# DynamixelController.net
KiCad netlist of a schematic drawn in EAGLE
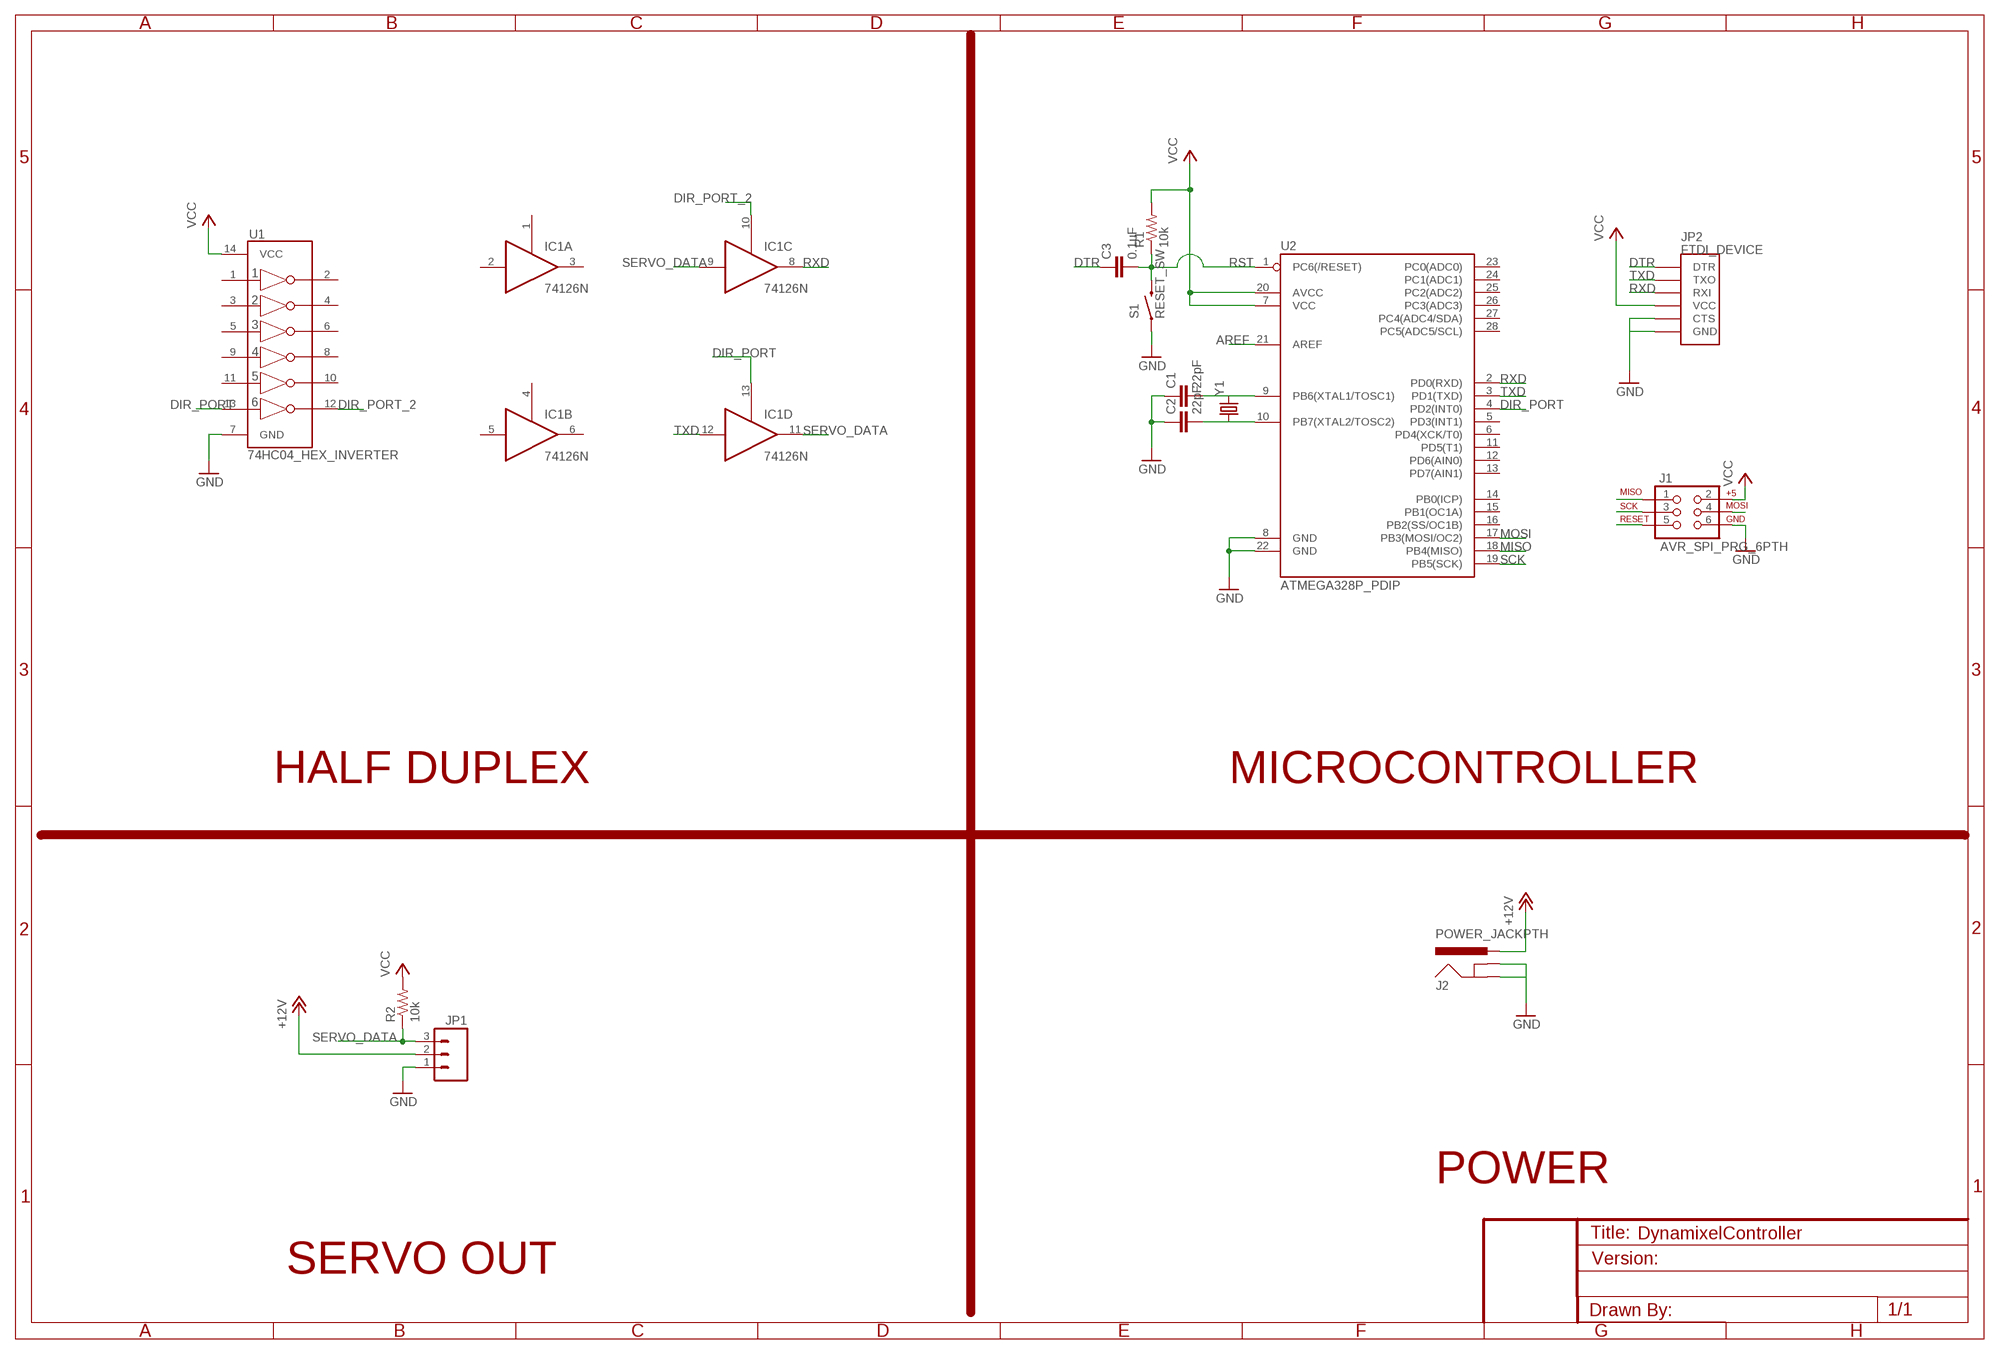
[diagram p0: schematic, sheet 1]

(export (version "E")
  (design (tool "Eeschema 10.0.6"))
  (components
    (comp (ref "C1")
      (value "22pF")
      (footprint "eagle-import:C050-024X044")
      (libsource (lib "eagle-import") (part "C-EU050-024X044"))
    )
    (comp (ref "C2")
      (value "22pF")
      (footprint "eagle-import:C050-024X044")
      (libsource (lib "eagle-import") (part "C-EU050-024X044"))
    )
    (comp (ref "C3")
      (value "0.1uF")
      (footprint "eagle-import:C050-024X044")
      (libsource (lib "eagle-import") (part "C-EU050-024X044"))
    )
    (comp (ref "IC1")
      (value "74126N")
      (footprint "eagle-import:DIL14")
      (libsource (lib "eagle-import") (part "74126N"))
    )
    (comp (ref "J1")
      (value "AVR_SPI_PRG_6PTH")
      (footprint "eagle-import:2X3")
      (libsource (lib "eagle-import") (part "AVR_SPI_PRG_6PTH"))
    )
    (comp (ref "J2")
      (value "POWER_JACKPTH")
      (footprint "eagle-import:POWER_JACK_PTH")
      (libsource (lib "eagle-import") (part "POWER_JACKPTH"))
    )
    (comp (ref "JP1")
      (value "M03POLAR")
      (footprint "eagle-import:MOLEX-1X3")
      (libsource (lib "eagle-import") (part "M03POLAR"))
    )
    (comp (ref "JP2")
      (value "FTDI_DEVICE")
      (footprint "eagle-import:FTDI_DEVICE_SIDE")
      (libsource (lib "eagle-import") (part "FTDI_DEVICE"))
    )
    (comp (ref "R1")
      (value "10k")
      (footprint "eagle-import:0207_7")
      (libsource (lib "eagle-import") (part "R-US_0207/7"))
    )
    (comp (ref "R2")
      (value "10k")
      (footprint "eagle-import:0207_7")
      (libsource (lib "eagle-import") (part "R-US_0207/7"))
    )
    (comp (ref "S1")
      (value "RESET_SW")
      (footprint "eagle-import:TACTILE-PTH")
      (libsource (lib "eagle-import") (part "SWITCH-MOMENTARY-2PTH"))
    )
    (comp (ref "U1")
      (value "74HC04_HEX_INVERTER")
      (footprint "eagle-import:DIL14")
      (libsource (lib "eagle-import") (part "74HC04_HEX_INVERTER"))
    )
    (comp (ref "U2")
      (value "ATMEGA328P_PDIP")
      (footprint "eagle-import:DIL28-3")
      (libsource (lib "eagle-import") (part "ATMEGA328P_PDIP"))
    )
    (comp (ref "Y1")
      (value "CRYSTALHC49US")
      (footprint "eagle-import:HC49US")
      (libsource (lib "eagle-import") (part "CRYSTALHC49US"))
    )
  )
  (nets
    (net (code "1") (name "+12V") (class "Default")
      (node (ref "J2") (pin "PWR") (pinfunction "PWR_PWR") (pintype "bidirectional"))
      (node (ref "JP1") (pin "2") (pinfunction "2_2") (pintype "passive"))
    )
    (net (code "2") (name "/AREF") (class "Default")
      (node (ref "U2") (pin "21") (pinfunction "AREF_21") (pintype "bidirectional"))
    )
    (net (code "3") (name "/DIR_PORT") (class "Default")
      (node (ref "IC1") (pin "13") (pinfunction "OE_13") (pintype "input"))
      (node (ref "U1") (pin "13") (pinfunction "6A_13") (pintype "input"))
      (node (ref "U2") (pin "4") (pinfunction "PD2(INT0)_4") (pintype "bidirectional"))
    )
    (net (code "4") (name "/DIR_PORT_2") (class "Default")
      (node (ref "IC1") (pin "10") (pinfunction "OE_10") (pintype "input"))
      (node (ref "U1") (pin "12") (pinfunction "6Y_12") (pintype "output"))
    )
    (net (code "5") (name "/DTR") (class "Default")
      (node (ref "C3") (pin "1") (pinfunction "1_1") (pintype "passive"))
      (node (ref "JP2") (pin "P$1") (pinfunction "DTR_P$1") (pintype "bidirectional"))
    )
    (net (code "6") (name "/MISO") (class "Default")
      (node (ref "J1") (pin "1") (pinfunction "1_1") (pintype "passive"))
      (node (ref "U2") (pin "18") (pinfunction "PB4(MISO)_18") (pintype "bidirectional"))
    )
    (net (code "7") (name "/MOSI") (class "Default")
      (node (ref "J1") (pin "4") (pinfunction "4_4") (pintype "passive"))
      (node (ref "U2") (pin "17") (pinfunction "PB3(MOSI/OC2)_17") (pintype "bidirectional"))
    )
    (net (code "8") (name "/RST") (class "Default")
      (node (ref "C3") (pin "2") (pinfunction "2_2") (pintype "passive"))
      (node (ref "J1") (pin "5") (pinfunction "5_5") (pintype "passive"))
      (node (ref "R1") (pin "1") (pinfunction "1_1") (pintype "passive"))
      (node (ref "S1") (pin "3") (pinfunction "2_3") (pintype "passive"))
      (node (ref "U2") (pin "1") (pinfunction "PC6(/RESET)_1") (pintype "bidirectional"))
    )
    (net (code "9") (name "/RXD") (class "Default")
      (node (ref "IC1") (pin "8") (pinfunction "O_8") (pintype "output"))
      (node (ref "JP2") (pin "P$3") (pinfunction "RXI_P$3") (pintype "bidirectional"))
      (node (ref "U2") (pin "2") (pinfunction "PD0(RXD)_2") (pintype "bidirectional"))
    )
    (net (code "10") (name "/SCK") (class "Default")
      (node (ref "J1") (pin "3") (pinfunction "3_3") (pintype "passive"))
      (node (ref "U2") (pin "19") (pinfunction "PB5(SCK)_19") (pintype "bidirectional"))
    )
    (net (code "11") (name "/SERVO_DATA") (class "Default")
      (node (ref "IC1") (pin "11") (pinfunction "O_11") (pintype "output"))
      (node (ref "IC1") (pin "9") (pinfunction "I_9") (pintype "input"))
      (node (ref "JP1") (pin "3") (pinfunction "3_3") (pintype "passive"))
      (node (ref "R2") (pin "1") (pinfunction "1_1") (pintype "passive"))
    )
    (net (code "12") (name "/TXD") (class "Default")
      (node (ref "IC1") (pin "12") (pinfunction "I_12") (pintype "input"))
      (node (ref "JP2") (pin "P$2") (pinfunction "TXO_P$2") (pintype "bidirectional"))
      (node (ref "U2") (pin "3") (pinfunction "PD1(TXD)_3") (pintype "bidirectional"))
    )
    (net (code "13") (name "GND") (class "Default")
      (node (ref "C1") (pin "1") (pinfunction "1_1") (pintype "passive"))
      (node (ref "C2") (pin "1") (pinfunction "1_1") (pintype "passive"))
      (node (ref "J1") (pin "6") (pinfunction "6_6") (pintype "passive"))
      (node (ref "J2") (pin "GND") (pinfunction "GND_GND") (pintype "bidirectional"))
      (node (ref "J2") (pin "GNDBREAK") (pinfunction "GNDBREAK_GNDBREAK") (pintype "bidirectional"))
      (node (ref "JP1") (pin "1") (pinfunction "1_1") (pintype "passive"))
      (node (ref "JP2") (pin "P$5") (pinfunction "CTS_P$5") (pintype "bidirectional"))
      (node (ref "JP2") (pin "P$6") (pinfunction "GND_P$6") (pintype "bidirectional"))
      (node (ref "S1") (pin "1") (pinfunction "1_1") (pintype "passive"))
      (node (ref "U1") (pin "7") (pinfunction "GND_7") (pintype "power_in"))
      (node (ref "U2") (pin "22") (pinfunction "GND_22") (pintype "bidirectional"))
      (node (ref "U2") (pin "8") (pinfunction "GND_8") (pintype "bidirectional"))
    )
    (net (code "14") (name "Net-(U2-PB6(XTAL1{slash}TOSC1))") (class "Default")
      (node (ref "C1") (pin "2") (pinfunction "2_2") (pintype "passive"))
      (node (ref "U2") (pin "9") (pinfunction "PB6(XTAL1/TOSC1)_9") (pintype "bidirectional"))
      (node (ref "Y1") (pin "2") (pinfunction "2_2") (pintype "passive"))
    )
    (net (code "15") (name "Net-(U2-PB7(XTAL2{slash}TOSC2))") (class "Default")
      (node (ref "C2") (pin "2") (pinfunction "2_2") (pintype "passive"))
      (node (ref "U2") (pin "10") (pinfunction "PB7(XTAL2/TOSC2)_10") (pintype "bidirectional"))
      (node (ref "Y1") (pin "1") (pinfunction "1_1") (pintype "passive"))
    )
    (net (code "16") (name "VCC") (class "Default")
      (node (ref "J1") (pin "2") (pinfunction "2_2") (pintype "passive"))
      (node (ref "JP2") (pin "P$4") (pinfunction "VCC_P$4") (pintype "bidirectional"))
      (node (ref "R1") (pin "2") (pinfunction "2_2") (pintype "passive"))
      (node (ref "R2") (pin "2") (pinfunction "2_2") (pintype "passive"))
      (node (ref "U1") (pin "14") (pinfunction "VCC_14") (pintype "power_in"))
      (node (ref "U2") (pin "20") (pinfunction "AVCC_20") (pintype "bidirectional"))
      (node (ref "U2") (pin "7") (pinfunction "VCC_7") (pintype "bidirectional"))
    )
    (net (code "17") (name "unconnected-(IC1A-I-Pad2)") (class "Default")
      (node (ref "IC1") (pin "2") (pinfunction "I_2") (pintype "input"))
    )
    (net (code "18") (name "unconnected-(IC1A-O-Pad3)") (class "Default")
      (node (ref "IC1") (pin "3") (pinfunction "O_3") (pintype "output"))
    )
    (net (code "19") (name "unconnected-(IC1A-OE-Pad1)") (class "Default")
      (node (ref "IC1") (pin "1") (pinfunction "OE_1") (pintype "input"))
    )
    (net (code "20") (name "unconnected-(IC1B-I-Pad5)") (class "Default")
      (node (ref "IC1") (pin "5") (pinfunction "I_5") (pintype "input"))
    )
    (net (code "21") (name "unconnected-(IC1B-O-Pad6)") (class "Default")
      (node (ref "IC1") (pin "6") (pinfunction "O_6") (pintype "output"))
    )
    (net (code "22") (name "unconnected-(IC1B-OE-Pad4)") (class "Default")
      (node (ref "IC1") (pin "4") (pinfunction "OE_4") (pintype "input"))
    )
    (net (code "23") (name "unconnected-(U1-1A-Pad1)") (class "Default")
      (node (ref "U1") (pin "1") (pinfunction "1A_1") (pintype "input"))
    )
    (net (code "24") (name "unconnected-(U1-1Y-Pad2)") (class "Default")
      (node (ref "U1") (pin "2") (pinfunction "1Y_2") (pintype "output"))
    )
    (net (code "25") (name "unconnected-(U1-2A-Pad3)") (class "Default")
      (node (ref "U1") (pin "3") (pinfunction "2A_3") (pintype "input"))
    )
    (net (code "26") (name "unconnected-(U1-2Y-Pad4)") (class "Default")
      (node (ref "U1") (pin "4") (pinfunction "2Y_4") (pintype "output"))
    )
    (net (code "27") (name "unconnected-(U1-3A-Pad5)") (class "Default")
      (node (ref "U1") (pin "5") (pinfunction "3A_5") (pintype "input"))
    )
    (net (code "28") (name "unconnected-(U1-3Y-Pad6)") (class "Default")
      (node (ref "U1") (pin "6") (pinfunction "3Y_6") (pintype "output"))
    )
    (net (code "29") (name "unconnected-(U1-4A-Pad9)") (class "Default")
      (node (ref "U1") (pin "9") (pinfunction "4A_9") (pintype "input"))
    )
    (net (code "30") (name "unconnected-(U1-4Y-Pad8)") (class "Default")
      (node (ref "U1") (pin "8") (pinfunction "4Y_8") (pintype "output"))
    )
    (net (code "31") (name "unconnected-(U1-5A-Pad11)") (class "Default")
      (node (ref "U1") (pin "11") (pinfunction "5A_11") (pintype "input"))
    )
    (net (code "32") (name "unconnected-(U1-5Y-Pad10)") (class "Default")
      (node (ref "U1") (pin "10") (pinfunction "5Y_10") (pintype "output"))
    )
    (net (code "33") (name "unconnected-(U2-PB0(ICP)-Pad14)") (class "Default")
      (node (ref "U2") (pin "14") (pinfunction "PB0(ICP)_14") (pintype "bidirectional"))
    )
    (net (code "34") (name "unconnected-(U2-PB1(OC1A)-Pad15)") (class "Default")
      (node (ref "U2") (pin "15") (pinfunction "PB1(OC1A)_15") (pintype "bidirectional"))
    )
    (net (code "35") (name "unconnected-(U2-PB2(SS{slash}OC1B)-Pad16)") (class "Default")
      (node (ref "U2") (pin "16") (pinfunction "PB2(SS/OC1B)_16") (pintype "bidirectional"))
    )
    (net (code "36") (name "unconnected-(U2-PC0(ADC0)-Pad23)") (class "Default")
      (node (ref "U2") (pin "23") (pinfunction "PC0(ADC0)_23") (pintype "bidirectional"))
    )
    (net (code "37") (name "unconnected-(U2-PC1(ADC1)-Pad24)") (class "Default")
      (node (ref "U2") (pin "24") (pinfunction "PC1(ADC1)_24") (pintype "bidirectional"))
    )
    (net (code "38") (name "unconnected-(U2-PC2(ADC2)-Pad25)") (class "Default")
      (node (ref "U2") (pin "25") (pinfunction "PC2(ADC2)_25") (pintype "bidirectional"))
    )
    (net (code "39") (name "unconnected-(U2-PC3(ADC3)-Pad26)") (class "Default")
      (node (ref "U2") (pin "26") (pinfunction "PC3(ADC3)_26") (pintype "bidirectional"))
    )
    (net (code "40") (name "unconnected-(U2-PC4(ADC4{slash}SDA)-Pad27)") (class "Default")
      (node (ref "U2") (pin "27") (pinfunction "PC4(ADC4/SDA)_27") (pintype "bidirectional"))
    )
    (net (code "41") (name "unconnected-(U2-PC5(ADC5{slash}SCL)-Pad28)") (class "Default")
      (node (ref "U2") (pin "28") (pinfunction "PC5(ADC5/SCL)_28") (pintype "bidirectional"))
    )
    (net (code "42") (name "unconnected-(U2-PD3(INT1)-Pad5)") (class "Default")
      (node (ref "U2") (pin "5") (pinfunction "PD3(INT1)_5") (pintype "bidirectional"))
    )
    (net (code "43") (name "unconnected-(U2-PD4(XCK{slash}T0)-Pad6)") (class "Default")
      (node (ref "U2") (pin "6") (pinfunction "PD4(XCK/T0)_6") (pintype "bidirectional"))
    )
    (net (code "44") (name "unconnected-(U2-PD5(T1)-Pad11)") (class "Default")
      (node (ref "U2") (pin "11") (pinfunction "PD5(T1)_11") (pintype "bidirectional"))
    )
    (net (code "45") (name "unconnected-(U2-PD6(AIN0)-Pad12)") (class "Default")
      (node (ref "U2") (pin "12") (pinfunction "PD6(AIN0)_12") (pintype "bidirectional"))
    )
    (net (code "46") (name "unconnected-(U2-PD7(AIN1)-Pad13)") (class "Default")
      (node (ref "U2") (pin "13") (pinfunction "PD7(AIN1)_13") (pintype "bidirectional"))
    )
  )
)
